# Video_Controller.net
KiCad netlist of a schematic drawn in EAGLE
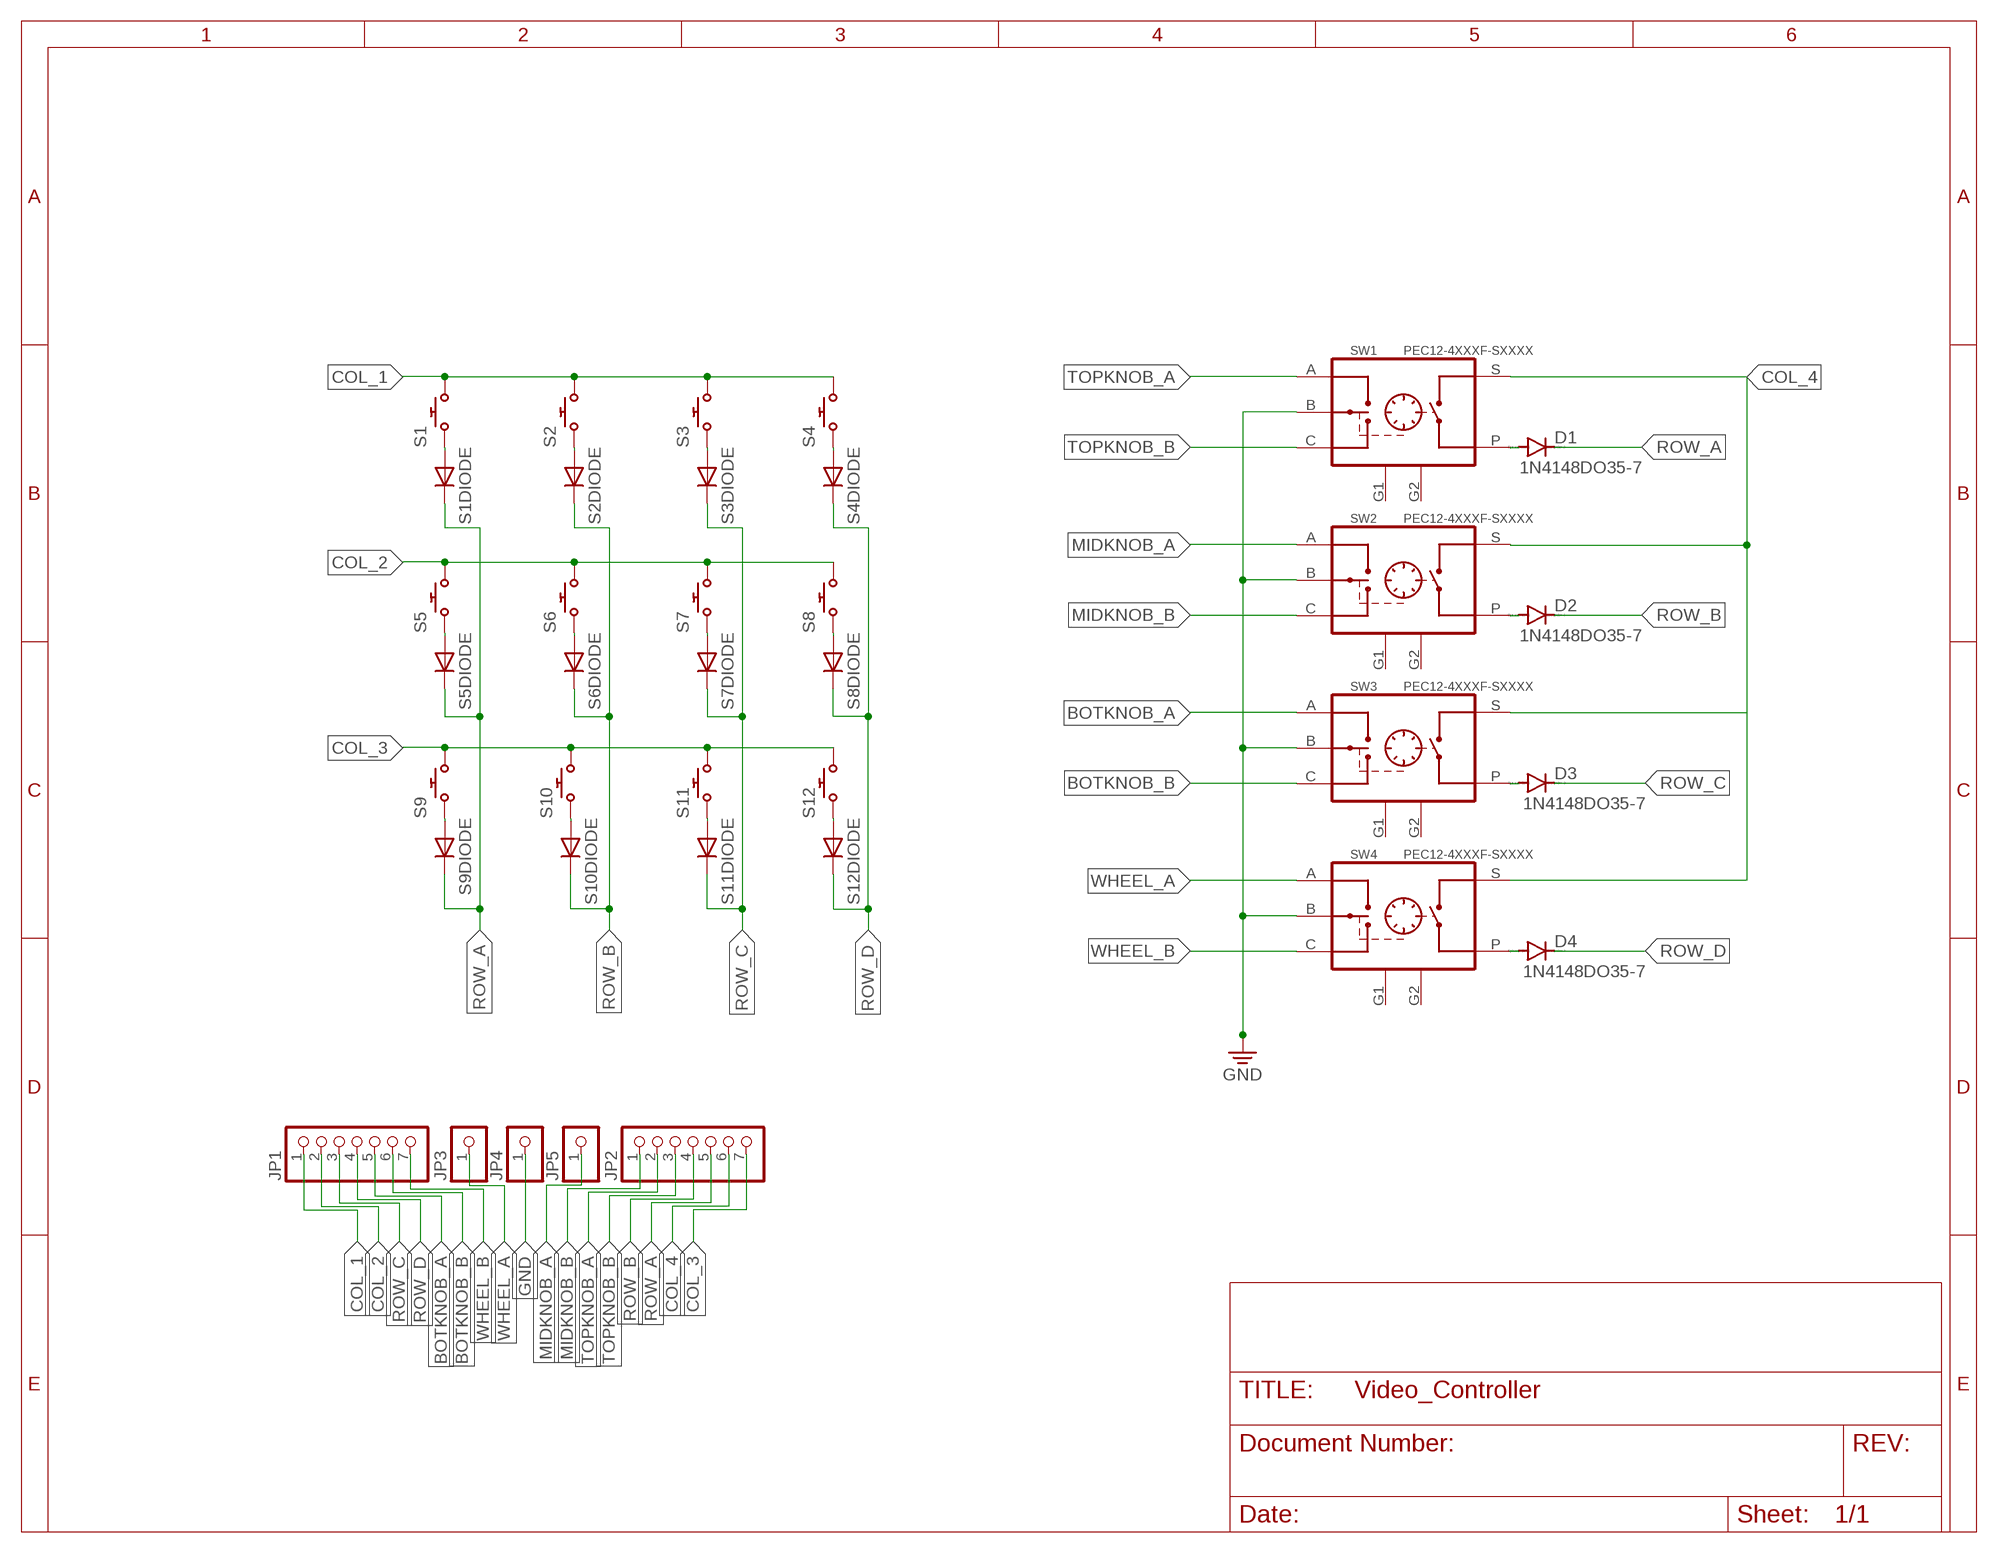
[diagram p0: schematic, sheet 1]

(export (version "E")
  (design (tool "Eeschema 10.0.6"))
  (components
    (comp (ref "D1")
      (value "1N4148DO35-7")
      (footprint "eagle-import:DO35-7")
      (libsource (lib "eagle-import") (part "1N4148DO35-7"))
    )
    (comp (ref "D2")
      (value "1N4148DO35-7")
      (footprint "eagle-import:DO35-7")
      (libsource (lib "eagle-import") (part "1N4148DO35-7"))
    )
    (comp (ref "D3")
      (value "1N4148DO35-7")
      (footprint "eagle-import:DO35-7")
      (libsource (lib "eagle-import") (part "1N4148DO35-7"))
    )
    (comp (ref "D4")
      (value "1N4148DO35-7")
      (footprint "eagle-import:DO35-7")
      (libsource (lib "eagle-import") (part "1N4148DO35-7"))
    )
    (comp (ref "JP1")
      (value "PINHD-1X7")
      (footprint "eagle-import:1X07")
      (libsource (lib "eagle-import") (part "PINHD-1X7"))
    )
    (comp (ref "JP2")
      (value "PINHD-1X7")
      (footprint "eagle-import:1X07")
      (libsource (lib "eagle-import") (part "PINHD-1X7"))
    )
    (comp (ref "JP3")
      (value "PINHD-1X1")
      (footprint "eagle-import:1X01")
      (libsource (lib "eagle-import") (part "PINHD-1X1"))
    )
    (comp (ref "JP4")
      (value "PINHD-1X1")
      (footprint "eagle-import:1X01")
      (libsource (lib "eagle-import") (part "PINHD-1X1"))
    )
    (comp (ref "JP5")
      (value "PINHD-1X1")
      (footprint "eagle-import:1X01")
      (libsource (lib "eagle-import") (part "PINHD-1X1"))
    )
    (comp (ref "S1")
      (value "CHERY_MX_DIODE")
      (footprint "eagle-import:CHERRY_MX_DIODE")
      (libsource (lib "eagle-import") (part "CHERY_MX_DIODE"))
    )
    (comp (ref "S2")
      (value "CHERY_MX_DIODE")
      (footprint "eagle-import:CHERRY_MX_DIODE")
      (libsource (lib "eagle-import") (part "CHERY_MX_DIODE"))
    )
    (comp (ref "S3")
      (value "CHERY_MX_DIODE")
      (footprint "eagle-import:CHERRY_MX_DIODE")
      (libsource (lib "eagle-import") (part "CHERY_MX_DIODE"))
    )
    (comp (ref "S4")
      (value "CHERY_MX_DIODE")
      (footprint "eagle-import:CHERRY_MX_DIODE")
      (libsource (lib "eagle-import") (part "CHERY_MX_DIODE"))
    )
    (comp (ref "S5")
      (value "CHERY_MX_DIODE")
      (footprint "eagle-import:CHERRY_MX_DIODE")
      (libsource (lib "eagle-import") (part "CHERY_MX_DIODE"))
    )
    (comp (ref "S6")
      (value "CHERY_MX_DIODE")
      (footprint "eagle-import:CHERRY_MX_DIODE")
      (libsource (lib "eagle-import") (part "CHERY_MX_DIODE"))
    )
    (comp (ref "S7")
      (value "CHERY_MX_DIODE")
      (footprint "eagle-import:CHERRY_MX_DIODE")
      (libsource (lib "eagle-import") (part "CHERY_MX_DIODE"))
    )
    (comp (ref "S8")
      (value "CHERY_MX_DIODE")
      (footprint "eagle-import:CHERRY_MX_DIODE")
      (libsource (lib "eagle-import") (part "CHERY_MX_DIODE"))
    )
    (comp (ref "S9")
      (value "CHERY_MX_DIODE")
      (footprint "eagle-import:CHERRY_MX_DIODE")
      (libsource (lib "eagle-import") (part "CHERY_MX_DIODE"))
    )
    (comp (ref "S10")
      (value "CHERY_MX_DIODE")
      (footprint "eagle-import:CHERRY_MX_DIODE")
      (libsource (lib "eagle-import") (part "CHERY_MX_DIODE"))
    )
    (comp (ref "S11")
      (value "CHERY_MX_DIODE")
      (footprint "eagle-import:CHERRY_MX_DIODE")
      (libsource (lib "eagle-import") (part "CHERY_MX_DIODE"))
    )
    (comp (ref "S12")
      (value "CHERY_MX_DIODE")
      (footprint "eagle-import:CHERRY_MX_DIODE")
      (libsource (lib "eagle-import") (part "CHERY_MX_DIODE"))
    )
    (comp (ref "SW1")
      (value "PEC12-4XXXF-SXXXX")
      (footprint "eagle-import:PEC12-4XXX")
      (libsource (lib "eagle-import") (part "PEC12-4XXXF-SXXXX"))
    )
    (comp (ref "SW2")
      (value "PEC12-4XXXF-SXXXX")
      (footprint "eagle-import:PEC12-4XXX")
      (libsource (lib "eagle-import") (part "PEC12-4XXXF-SXXXX"))
    )
    (comp (ref "SW3")
      (value "PEC12-4XXXF-SXXXX")
      (footprint "eagle-import:PEC12-4XXX")
      (libsource (lib "eagle-import") (part "PEC12-4XXXF-SXXXX"))
    )
    (comp (ref "SW4")
      (value "PEC12-4XXXF-SXXXX")
      (footprint "eagle-import:PEC12-4XXX")
      (libsource (lib "eagle-import") (part "PEC12-4XXXF-SXXXX"))
    )
  )
  (nets
    (net (code "1") (name "BOTKNOB_A") (class "Default")
      (node (ref "JP1") (pin "5") (pinfunction "5_5") (pintype "passive"))
      (node (ref "SW3") (pin "A") (pinfunction "A_A") (pintype "passive"))
    )
    (net (code "2") (name "BOTKNOB_B") (class "Default")
      (node (ref "JP1") (pin "6") (pinfunction "6_6") (pintype "passive"))
      (node (ref "SW3") (pin "C") (pinfunction "C_C") (pintype "passive"))
    )
    (net (code "3") (name "COL_1") (class "Default")
      (node (ref "JP1") (pin "1") (pinfunction "1_1") (pintype "passive"))
      (node (ref "S1") (pin "S2") (pinfunction "2_S2") (pintype "passive"))
      (node (ref "S2") (pin "S2") (pinfunction "2_S2") (pintype "passive"))
      (node (ref "S3") (pin "S2") (pinfunction "2_S2") (pintype "passive"))
      (node (ref "S4") (pin "S2") (pinfunction "2_S2") (pintype "passive"))
    )
    (net (code "4") (name "COL_2") (class "Default")
      (node (ref "JP1") (pin "2") (pinfunction "2_2") (pintype "passive"))
      (node (ref "S5") (pin "S2") (pinfunction "2_S2") (pintype "passive"))
      (node (ref "S6") (pin "S2") (pinfunction "2_S2") (pintype "passive"))
      (node (ref "S7") (pin "S2") (pinfunction "2_S2") (pintype "passive"))
      (node (ref "S8") (pin "S2") (pinfunction "2_S2") (pintype "passive"))
    )
    (net (code "5") (name "COL_3") (class "Default")
      (node (ref "JP2") (pin "7") (pinfunction "7_7") (pintype "passive"))
      (node (ref "S10") (pin "S2") (pinfunction "2_S2") (pintype "passive"))
      (node (ref "S11") (pin "S2") (pinfunction "2_S2") (pintype "passive"))
      (node (ref "S12") (pin "S2") (pinfunction "2_S2") (pintype "passive"))
      (node (ref "S9") (pin "S2") (pinfunction "2_S2") (pintype "passive"))
    )
    (net (code "6") (name "COL_4") (class "Default")
      (node (ref "JP2") (pin "6") (pinfunction "6_6") (pintype "passive"))
      (node (ref "SW1") (pin "S") (pinfunction "S_S") (pintype "passive"))
    )
    (net (code "7") (name "GND") (class "Default")
      (node (ref "JP4") (pin "1") (pinfunction "1_1") (pintype "passive"))
      (node (ref "SW1") (pin "B") (pinfunction "B_B") (pintype "passive"))
      (node (ref "SW2") (pin "B") (pinfunction "B_B") (pintype "passive"))
      (node (ref "SW3") (pin "B") (pinfunction "B_B") (pintype "passive"))
      (node (ref "SW4") (pin "B") (pinfunction "B_B") (pintype "passive"))
    )
    (net (code "8") (name "MIDKNOB_A") (class "Default")
      (node (ref "JP5") (pin "1") (pinfunction "1_1") (pintype "passive"))
      (node (ref "SW2") (pin "A") (pinfunction "A_A") (pintype "passive"))
    )
    (net (code "9") (name "MIDKNOB_B") (class "Default")
      (node (ref "JP2") (pin "1") (pinfunction "1_1") (pintype "passive"))
      (node (ref "SW2") (pin "C") (pinfunction "C_C") (pintype "passive"))
    )
    (net (code "10") (name "Net-(D1-PadA)") (class "Default")
      (node (ref "D1") (pin "A") (pinfunction "A_A") (pintype "passive"))
      (node (ref "SW1") (pin "P") (pinfunction "P_P") (pintype "passive"))
    )
    (net (code "11") (name "Net-(D2-PadA)") (class "Default")
      (node (ref "D2") (pin "A") (pinfunction "A_A") (pintype "passive"))
      (node (ref "SW2") (pin "P") (pinfunction "P_P") (pintype "passive"))
    )
    (net (code "12") (name "Net-(D3-PadA)") (class "Default")
      (node (ref "D3") (pin "A") (pinfunction "A_A") (pintype "passive"))
      (node (ref "SW3") (pin "P") (pinfunction "P_P") (pintype "passive"))
    )
    (net (code "13") (name "Net-(D4-PadA)") (class "Default")
      (node (ref "D4") (pin "A") (pinfunction "A_A") (pintype "passive"))
      (node (ref "SW4") (pin "P") (pinfunction "P_P") (pintype "passive"))
    )
    (net (code "14") (name "Net-(S1A-A)") (class "Default")
      (node (ref "S1") (pin "D1") (pinfunction "A_D1") (pintype "passive"))
      (node (ref "S1") (pin "S1") (pinfunction "1_S1") (pintype "passive"))
    )
    (net (code "15") (name "Net-(S2A-A)") (class "Default")
      (node (ref "S2") (pin "D1") (pinfunction "A_D1") (pintype "passive"))
      (node (ref "S2") (pin "S1") (pinfunction "1_S1") (pintype "passive"))
    )
    (net (code "16") (name "Net-(S3A-A)") (class "Default")
      (node (ref "S3") (pin "D1") (pinfunction "A_D1") (pintype "passive"))
      (node (ref "S3") (pin "S1") (pinfunction "1_S1") (pintype "passive"))
    )
    (net (code "17") (name "Net-(S4A-A)") (class "Default")
      (node (ref "S4") (pin "D1") (pinfunction "A_D1") (pintype "passive"))
      (node (ref "S4") (pin "S1") (pinfunction "1_S1") (pintype "passive"))
    )
    (net (code "18") (name "Net-(S5A-A)") (class "Default")
      (node (ref "S5") (pin "D1") (pinfunction "A_D1") (pintype "passive"))
      (node (ref "S5") (pin "S1") (pinfunction "1_S1") (pintype "passive"))
    )
    (net (code "19") (name "Net-(S6A-A)") (class "Default")
      (node (ref "S6") (pin "D1") (pinfunction "A_D1") (pintype "passive"))
      (node (ref "S6") (pin "S1") (pinfunction "1_S1") (pintype "passive"))
    )
    (net (code "20") (name "Net-(S7A-A)") (class "Default")
      (node (ref "S7") (pin "D1") (pinfunction "A_D1") (pintype "passive"))
      (node (ref "S7") (pin "S1") (pinfunction "1_S1") (pintype "passive"))
    )
    (net (code "21") (name "Net-(S8A-A)") (class "Default")
      (node (ref "S8") (pin "D1") (pinfunction "A_D1") (pintype "passive"))
      (node (ref "S8") (pin "S1") (pinfunction "1_S1") (pintype "passive"))
    )
    (net (code "22") (name "Net-(S9A-A)") (class "Default")
      (node (ref "S9") (pin "D1") (pinfunction "A_D1") (pintype "passive"))
      (node (ref "S9") (pin "S1") (pinfunction "1_S1") (pintype "passive"))
    )
    (net (code "23") (name "Net-(S10A-A)") (class "Default")
      (node (ref "S10") (pin "D1") (pinfunction "A_D1") (pintype "passive"))
      (node (ref "S10") (pin "S1") (pinfunction "1_S1") (pintype "passive"))
    )
    (net (code "24") (name "Net-(S11A-A)") (class "Default")
      (node (ref "S11") (pin "D1") (pinfunction "A_D1") (pintype "passive"))
      (node (ref "S11") (pin "S1") (pinfunction "1_S1") (pintype "passive"))
    )
    (net (code "25") (name "Net-(S12A-A)") (class "Default")
      (node (ref "S12") (pin "D1") (pinfunction "A_D1") (pintype "passive"))
      (node (ref "S12") (pin "S1") (pinfunction "1_S1") (pintype "passive"))
    )
    (net (code "26") (name "Net-(SW2-PadS)") (class "Default")
      (node (ref "SW2") (pin "S") (pinfunction "S_S") (pintype "passive"))
      (node (ref "SW3") (pin "S") (pinfunction "S_S") (pintype "passive"))
      (node (ref "SW4") (pin "S") (pinfunction "S_S") (pintype "passive"))
    )
    (net (code "27") (name "ROW_A") (class "Default")
      (node (ref "D1") (pin "C") (pinfunction "C_C") (pintype "passive"))
      (node (ref "JP2") (pin "5") (pinfunction "5_5") (pintype "passive"))
      (node (ref "S1") (pin "D2") (pinfunction "C_D2") (pintype "passive"))
      (node (ref "S5") (pin "D2") (pinfunction "C_D2") (pintype "passive"))
      (node (ref "S9") (pin "D2") (pinfunction "C_D2") (pintype "passive"))
    )
    (net (code "28") (name "ROW_B") (class "Default")
      (node (ref "D2") (pin "C") (pinfunction "C_C") (pintype "passive"))
      (node (ref "JP2") (pin "4") (pinfunction "4_4") (pintype "passive"))
      (node (ref "S10") (pin "D2") (pinfunction "C_D2") (pintype "passive"))
      (node (ref "S2") (pin "D2") (pinfunction "C_D2") (pintype "passive"))
      (node (ref "S6") (pin "D2") (pinfunction "C_D2") (pintype "passive"))
    )
    (net (code "29") (name "ROW_C") (class "Default")
      (node (ref "D3") (pin "C") (pinfunction "C_C") (pintype "passive"))
      (node (ref "JP1") (pin "3") (pinfunction "3_3") (pintype "passive"))
      (node (ref "S11") (pin "D2") (pinfunction "C_D2") (pintype "passive"))
      (node (ref "S3") (pin "D2") (pinfunction "C_D2") (pintype "passive"))
      (node (ref "S7") (pin "D2") (pinfunction "C_D2") (pintype "passive"))
    )
    (net (code "30") (name "ROW_D") (class "Default")
      (node (ref "D4") (pin "C") (pinfunction "C_C") (pintype "passive"))
      (node (ref "JP1") (pin "4") (pinfunction "4_4") (pintype "passive"))
      (node (ref "S12") (pin "D2") (pinfunction "C_D2") (pintype "passive"))
      (node (ref "S4") (pin "D2") (pinfunction "C_D2") (pintype "passive"))
      (node (ref "S8") (pin "D2") (pinfunction "C_D2") (pintype "passive"))
    )
    (net (code "31") (name "TOPKNOB_A") (class "Default")
      (node (ref "JP2") (pin "2") (pinfunction "2_2") (pintype "passive"))
      (node (ref "SW1") (pin "A") (pinfunction "A_A") (pintype "passive"))
    )
    (net (code "32") (name "TOPKNOB_B") (class "Default")
      (node (ref "JP2") (pin "3") (pinfunction "3_3") (pintype "passive"))
      (node (ref "SW1") (pin "C") (pinfunction "C_C") (pintype "passive"))
    )
    (net (code "33") (name "WHEEL_A") (class "Default")
      (node (ref "JP3") (pin "1") (pinfunction "1_1") (pintype "passive"))
      (node (ref "SW4") (pin "A") (pinfunction "A_A") (pintype "passive"))
    )
    (net (code "34") (name "WHEEL_B") (class "Default")
      (node (ref "JP1") (pin "7") (pinfunction "7_7") (pintype "passive"))
      (node (ref "SW4") (pin "C") (pinfunction "C_C") (pintype "passive"))
    )
    (net (code "35") (name "unconnected-(SW1-PadG1)") (class "Default")
      (node (ref "SW1") (pin "G1") (pinfunction "G1_G1") (pintype "passive"))
    )
    (net (code "36") (name "unconnected-(SW1-PadG2)") (class "Default")
      (node (ref "SW1") (pin "G2") (pinfunction "G2_G2") (pintype "passive"))
    )
    (net (code "37") (name "unconnected-(SW2-PadG1)") (class "Default")
      (node (ref "SW2") (pin "G1") (pinfunction "G1_G1") (pintype "passive"))
    )
    (net (code "38") (name "unconnected-(SW2-PadG2)") (class "Default")
      (node (ref "SW2") (pin "G2") (pinfunction "G2_G2") (pintype "passive"))
    )
    (net (code "39") (name "unconnected-(SW3-PadG1)") (class "Default")
      (node (ref "SW3") (pin "G1") (pinfunction "G1_G1") (pintype "passive"))
    )
    (net (code "40") (name "unconnected-(SW3-PadG2)") (class "Default")
      (node (ref "SW3") (pin "G2") (pinfunction "G2_G2") (pintype "passive"))
    )
    (net (code "41") (name "unconnected-(SW4-PadG1)") (class "Default")
      (node (ref "SW4") (pin "G1") (pinfunction "G1_G1") (pintype "passive"))
    )
    (net (code "42") (name "unconnected-(SW4-PadG2)") (class "Default")
      (node (ref "SW4") (pin "G2") (pinfunction "G2_G2") (pintype "passive"))
    )
  )
)
